# LevelShiftADC.net
KiCad netlist of a schematic drawn in Altium Designer
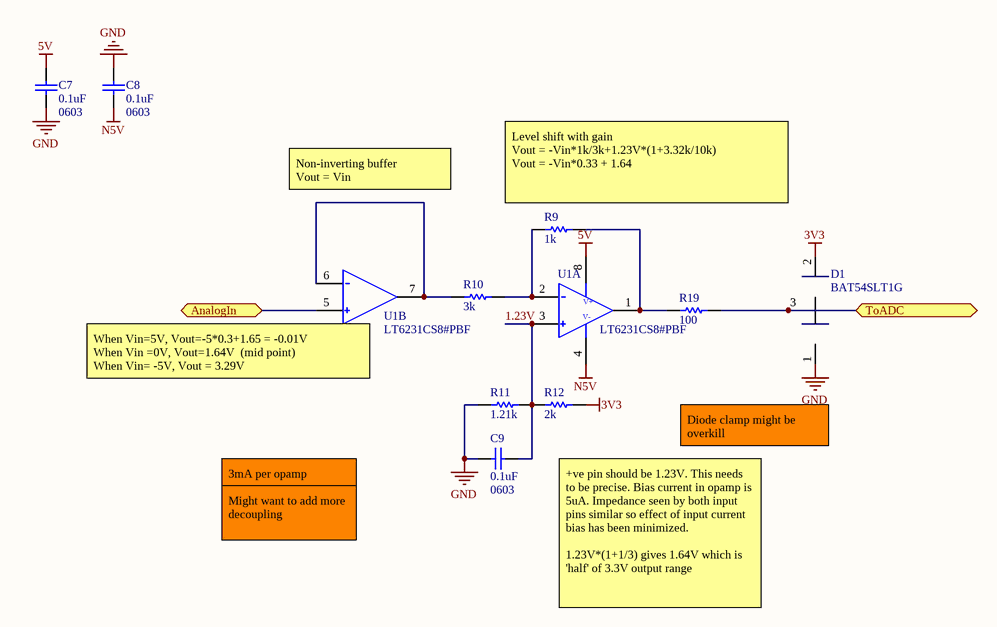
[diagram p0: LevelShiftADC.SchDoc]

(export (version "E")
  (design (tool "Eeschema 10.0.6"))
  (components
    (comp (ref "C7")
      (value "0.1uF")
      (footprint "0603")
      (description "Capacitor, Ceramic, 0603")
      (fields
        (field (name "MANUFACTURER") "Samsung Electro-Mechanics")
        (field (name "MANUFACTURERS PART NUMBER") "CL10A104KA8NNNC")
      )
      (libsource (lib "projectlibrary") (part "Cap0603"))
    )
    (comp (ref "C8")
      (value "0.1uF")
      (footprint "0603")
      (description "Capacitor, Ceramic, 0603")
      (fields
        (field (name "MANUFACTURER") "Samsung Electro-Mechanics")
        (field (name "MANUFACTURERS PART NUMBER") "CL10A104KA8NNNC")
      )
      (libsource (lib "projectlibrary") (part "Cap0603"))
    )
    (comp (ref "C9")
      (value "0.1uF")
      (footprint "0603")
      (description "Capacitor, Ceramic, 0603")
      (fields
        (field (name "MANUFACTURER") "Samsung Electro-Mechanics")
        (field (name "MANUFACTURERS PART NUMBER") "CL10A104KA8NNNC")
      )
      (libsource (lib "projectlibrary") (part "Cap0603"))
    )
    (comp (ref "D1")
      (value "BAT54SLT1G")
      (footprint "SOT23")
      (fields (field (name "MANUFACTURER") "ON Semiconductor"))
      (libsource (lib "projectlibrary") (part "DiodeClamp"))
    )
    (comp (ref "R9")
      (value "1k")
      (footprint "0603")
      (description "Resistor")
      (fields
        (field (name "MANUFACTURER") "Yageo")
        (field (name "MANUFACTURERS PART NUMBER") "RC0603FR-071KL")
      )
      (libsource (lib "projectlibrary") (part "Res0603"))
    )
    (comp (ref "R10")
      (value "3k")
      (footprint "0603")
      (description "Resistor")
      (fields
        (field (name "MANUFACTURER") "Vishay Dale")
        (field (name "MANUFACTURERS PART NUMBER") "CRCW06033K00FKEAC")
      )
      (libsource (lib "projectlibrary") (part "Res0603"))
    )
    (comp (ref "R11")
      (value "1.21k")
      (footprint "0603")
      (description "Resistor")
      (fields
        (field (name "MANUFACTURER") "Yageo")
        (field (name "MANUFACTURERS PART NUMBER") "RMCF0603FT1K21")
      )
      (libsource (lib "projectlibrary") (part "Res0603"))
    )
    (comp (ref "R12")
      (value "2k")
      (footprint "0603")
      (description "Resistor")
      (fields
        (field (name "MANUFACTURER") "Vishay Dale")
        (field (name "MANUFACTURERS PART NUMBER") "CRCW06032K00FKEAC")
      )
      (libsource (lib "projectlibrary") (part "Res0603"))
    )
    (comp (ref "R19")
      (value "100")
      (footprint "0603")
      (description "Resistor")
      (fields
        (field (name "MANUFACTURER") "Yageo")
        (field (name "MANUFACTURERS PART NUMBER") "RC0603FR-07100RL")
      )
      (libsource (lib "projectlibrary") (part "Res0603"))
    )
    (comp (ref "U1")
      (value "LT6231CS8#PBF")
      (footprint "SO8")
      (description "Dual R-R Opamp Soic 8 215Mhz GBP")
      (fields
        (field (name "MANUFACTURERS PART NUMBER") "LT6231CS8")
        (field (name "MANUFACTURER") "Linear Technology/Analog Devices")
      )
      (libsource (lib "projectlibrary") (part "TSH82IYDT"))
    )
  )
  (nets
    (net (code "1") (name "/1.23V") (class "Default")
      (node (ref "C9") (pin "2") (pinfunction "2_2") (pintype "passive"))
      (node (ref "R11") (pin "2") (pinfunction "2_2") (pintype "passive"))
      (node (ref "R12") (pin "1") (pinfunction "1_1") (pintype "passive"))
      (node (ref "U1") (pin "3") (pinfunction "IN+_3") (pintype "passive"))
    )
    (net (code "2") (name "/AnalogIn") (class "Default")
      (node (ref "U1") (pin "5") (pinfunction "IN+_5") (pintype "passive"))
    )
    (net (code "3") (name "/ToADC") (class "Default")
      (node (ref "D1") (pin "3") (pinfunction "3_3") (pintype "passive"))
      (node (ref "R19") (pin "2") (pinfunction "2_2") (pintype "passive"))
    )
    (net (code "4") (name "3V3") (class "Default")
      (node (ref "D1") (pin "2") (pinfunction "2_2") (pintype "passive"))
      (node (ref "R12") (pin "2") (pinfunction "2_2") (pintype "passive"))
    )
    (net (code "5") (name "5V") (class "Default")
      (node (ref "C7") (pin "2") (pinfunction "2_2") (pintype "passive"))
      (node (ref "U1") (pin "8") (pinfunction "V+_8") (pintype "power_in"))
    )
    (net (code "6") (name "GND") (class "Default")
      (node (ref "C7") (pin "1") (pinfunction "1_1") (pintype "passive"))
      (node (ref "C8") (pin "2") (pinfunction "2_2") (pintype "passive"))
      (node (ref "C9") (pin "1") (pinfunction "1_1") (pintype "passive"))
      (node (ref "D1") (pin "1") (pinfunction "1_1") (pintype "passive"))
      (node (ref "R11") (pin "1") (pinfunction "1_1") (pintype "passive"))
    )
    (net (code "7") (name "N5V") (class "Default")
      (node (ref "C8") (pin "1") (pinfunction "1_1") (pintype "passive"))
      (node (ref "U1") (pin "4") (pinfunction "V-_4") (pintype "power_in"))
    )
    (net (code "8") (name "Net-(U1A-IN-)") (class "Default")
      (node (ref "R10") (pin "2") (pinfunction "2_2") (pintype "passive"))
      (node (ref "R9") (pin "1") (pinfunction "1_1") (pintype "passive"))
      (node (ref "U1") (pin "2") (pinfunction "IN-_2") (pintype "passive"))
    )
    (net (code "9") (name "Net-(U1A-Out)") (class "Default")
      (node (ref "R19") (pin "1") (pinfunction "1_1") (pintype "passive"))
      (node (ref "R9") (pin "2") (pinfunction "2_2") (pintype "passive"))
      (node (ref "U1") (pin "1") (pinfunction "Out_1") (pintype "passive"))
    )
    (net (code "10") (name "Net-(U1B-IN-)") (class "Default")
      (node (ref "R10") (pin "1") (pinfunction "1_1") (pintype "passive"))
      (node (ref "U1") (pin "6") (pinfunction "IN-_6") (pintype "passive"))
      (node (ref "U1") (pin "7") (pinfunction "Out_7") (pintype "passive"))
    )
  )
)
